# weaver_4pin_merger.net
KiCad netlist of a schematic drawn in EAGLE
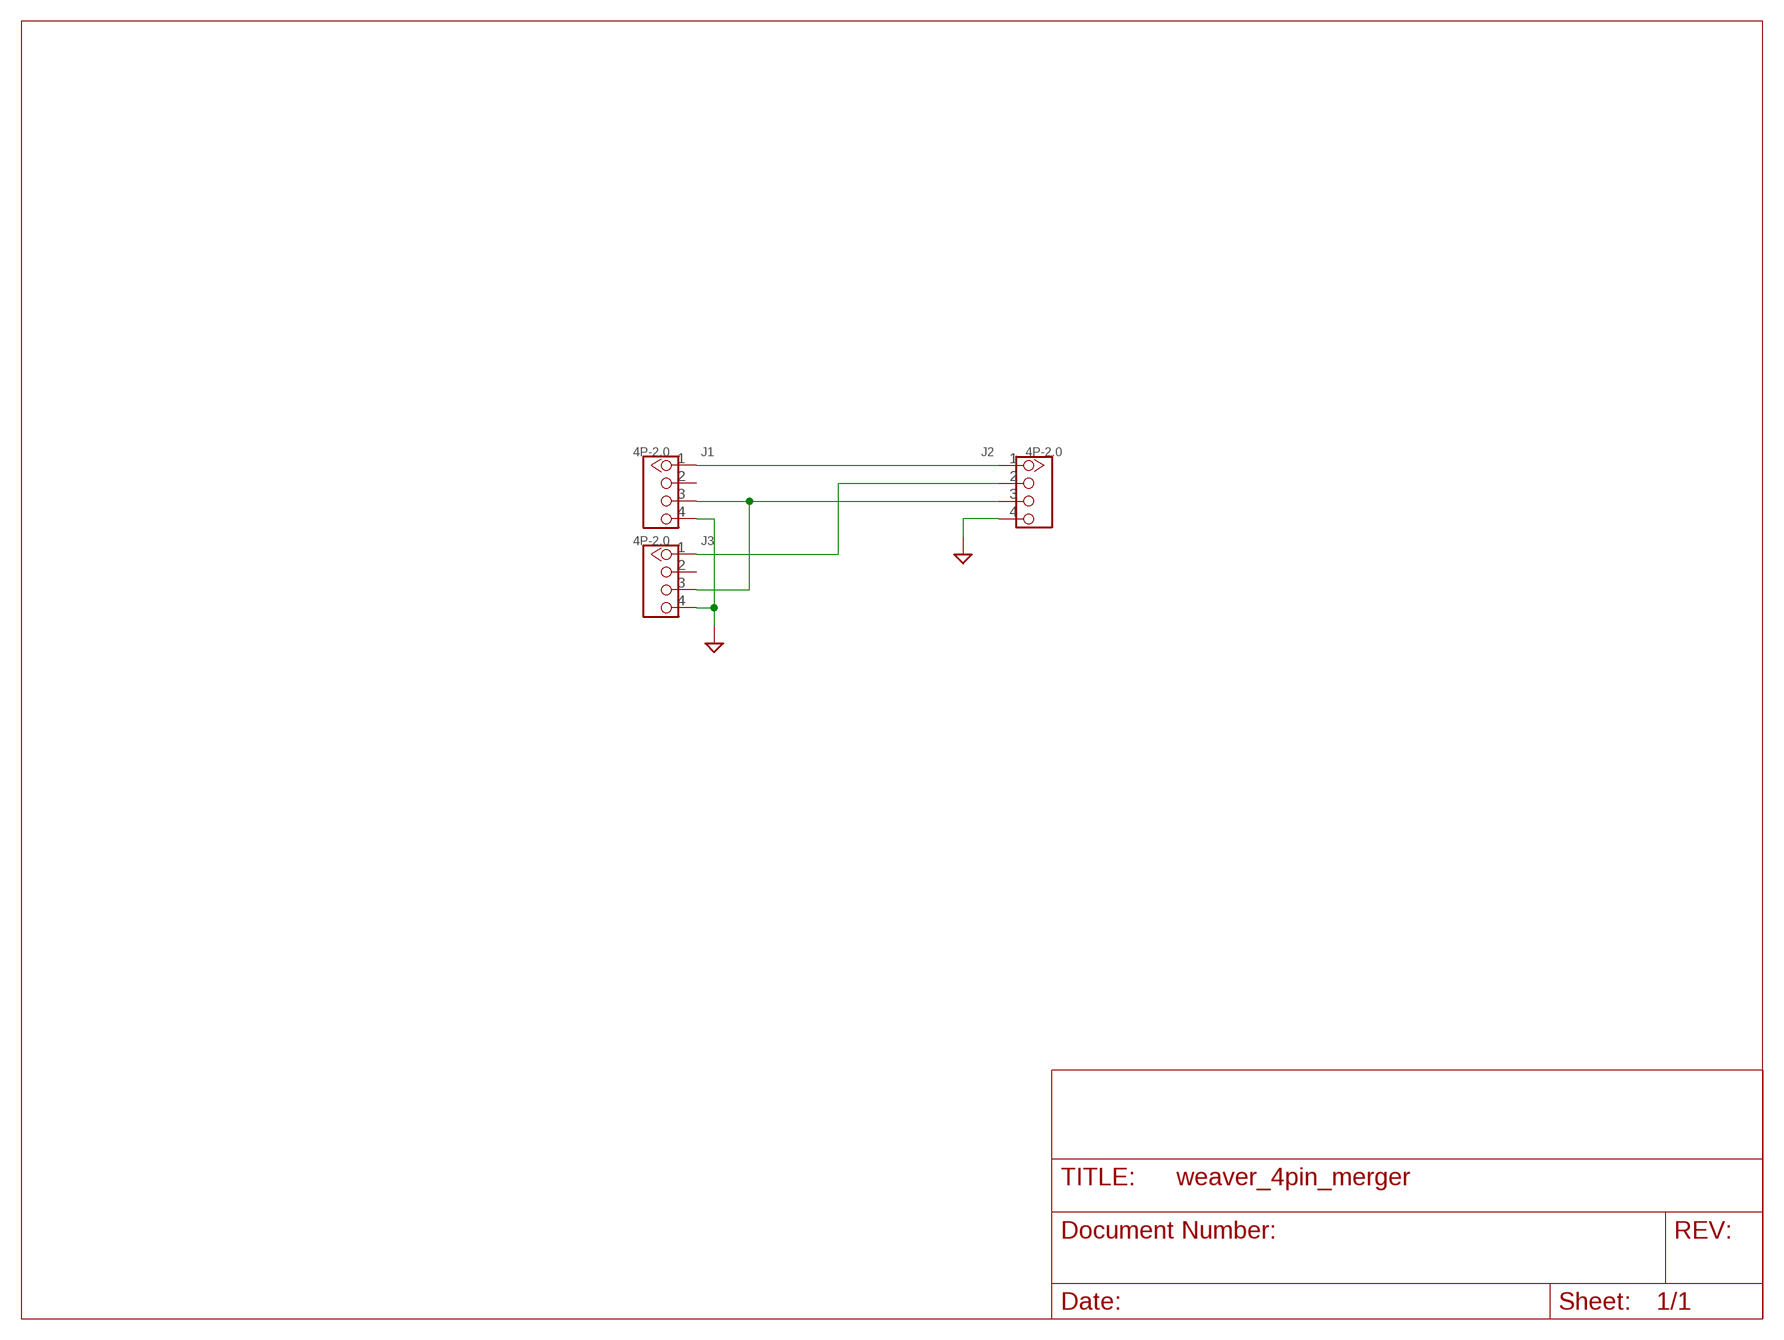
[diagram p0: schematic, sheet 1]

(export (version "E")
  (design (tool "Eeschema 10.0.6"))
  (components
    (comp (ref "J1")
      (value "4P-2.0")
      (footprint "eagle-import:HW4-2.0")
      (libsource (lib "eagle-import") (part "GROVE-CONNECTOR-DIP(4P-2.0)"))
    )
    (comp (ref "J2")
      (value "4P-2.0")
      (footprint "eagle-import:HW4-2.0")
      (libsource (lib "eagle-import") (part "GROVE-CONNECTOR-DIP(4P-2.0)"))
    )
    (comp (ref "J3")
      (value "4P-2.0")
      (footprint "eagle-import:HW4-2.0")
      (libsource (lib "eagle-import") (part "GROVE-CONNECTOR-DIP(4P-2.0)"))
    )
  )
  (nets
    (net (code "1") (name "GND") (class "Default")
      (node (ref "J1") (pin "4") (pinfunction "4_4") (pintype "bidirectional"))
      (node (ref "J2") (pin "4") (pinfunction "4_4") (pintype "bidirectional"))
      (node (ref "J3") (pin "4") (pinfunction "4_4") (pintype "bidirectional"))
    )
    (net (code "2") (name "Net-(J1-Pad1)") (class "Default")
      (node (ref "J1") (pin "1") (pinfunction "1_1") (pintype "bidirectional"))
      (node (ref "J2") (pin "1") (pinfunction "1_1") (pintype "bidirectional"))
    )
    (net (code "3") (name "Net-(J1-Pad3)") (class "Default")
      (node (ref "J1") (pin "3") (pinfunction "3_3") (pintype "bidirectional"))
      (node (ref "J2") (pin "3") (pinfunction "3_3") (pintype "bidirectional"))
      (node (ref "J3") (pin "3") (pinfunction "3_3") (pintype "bidirectional"))
    )
    (net (code "4") (name "Net-(J2-Pad2)") (class "Default")
      (node (ref "J2") (pin "2") (pinfunction "2_2") (pintype "bidirectional"))
      (node (ref "J3") (pin "1") (pinfunction "1_1") (pintype "bidirectional"))
    )
    (net (code "5") (name "unconnected-(J1-Pad2)") (class "Default")
      (node (ref "J1") (pin "2") (pinfunction "2_2") (pintype "bidirectional"))
    )
    (net (code "6") (name "unconnected-(J3-Pad2)") (class "Default")
      (node (ref "J3") (pin "2") (pinfunction "2_2") (pintype "bidirectional"))
    )
  )
)
